# FPGA_Systems_Program.net
KiCad netlist of a schematic drawn in Altium Designer
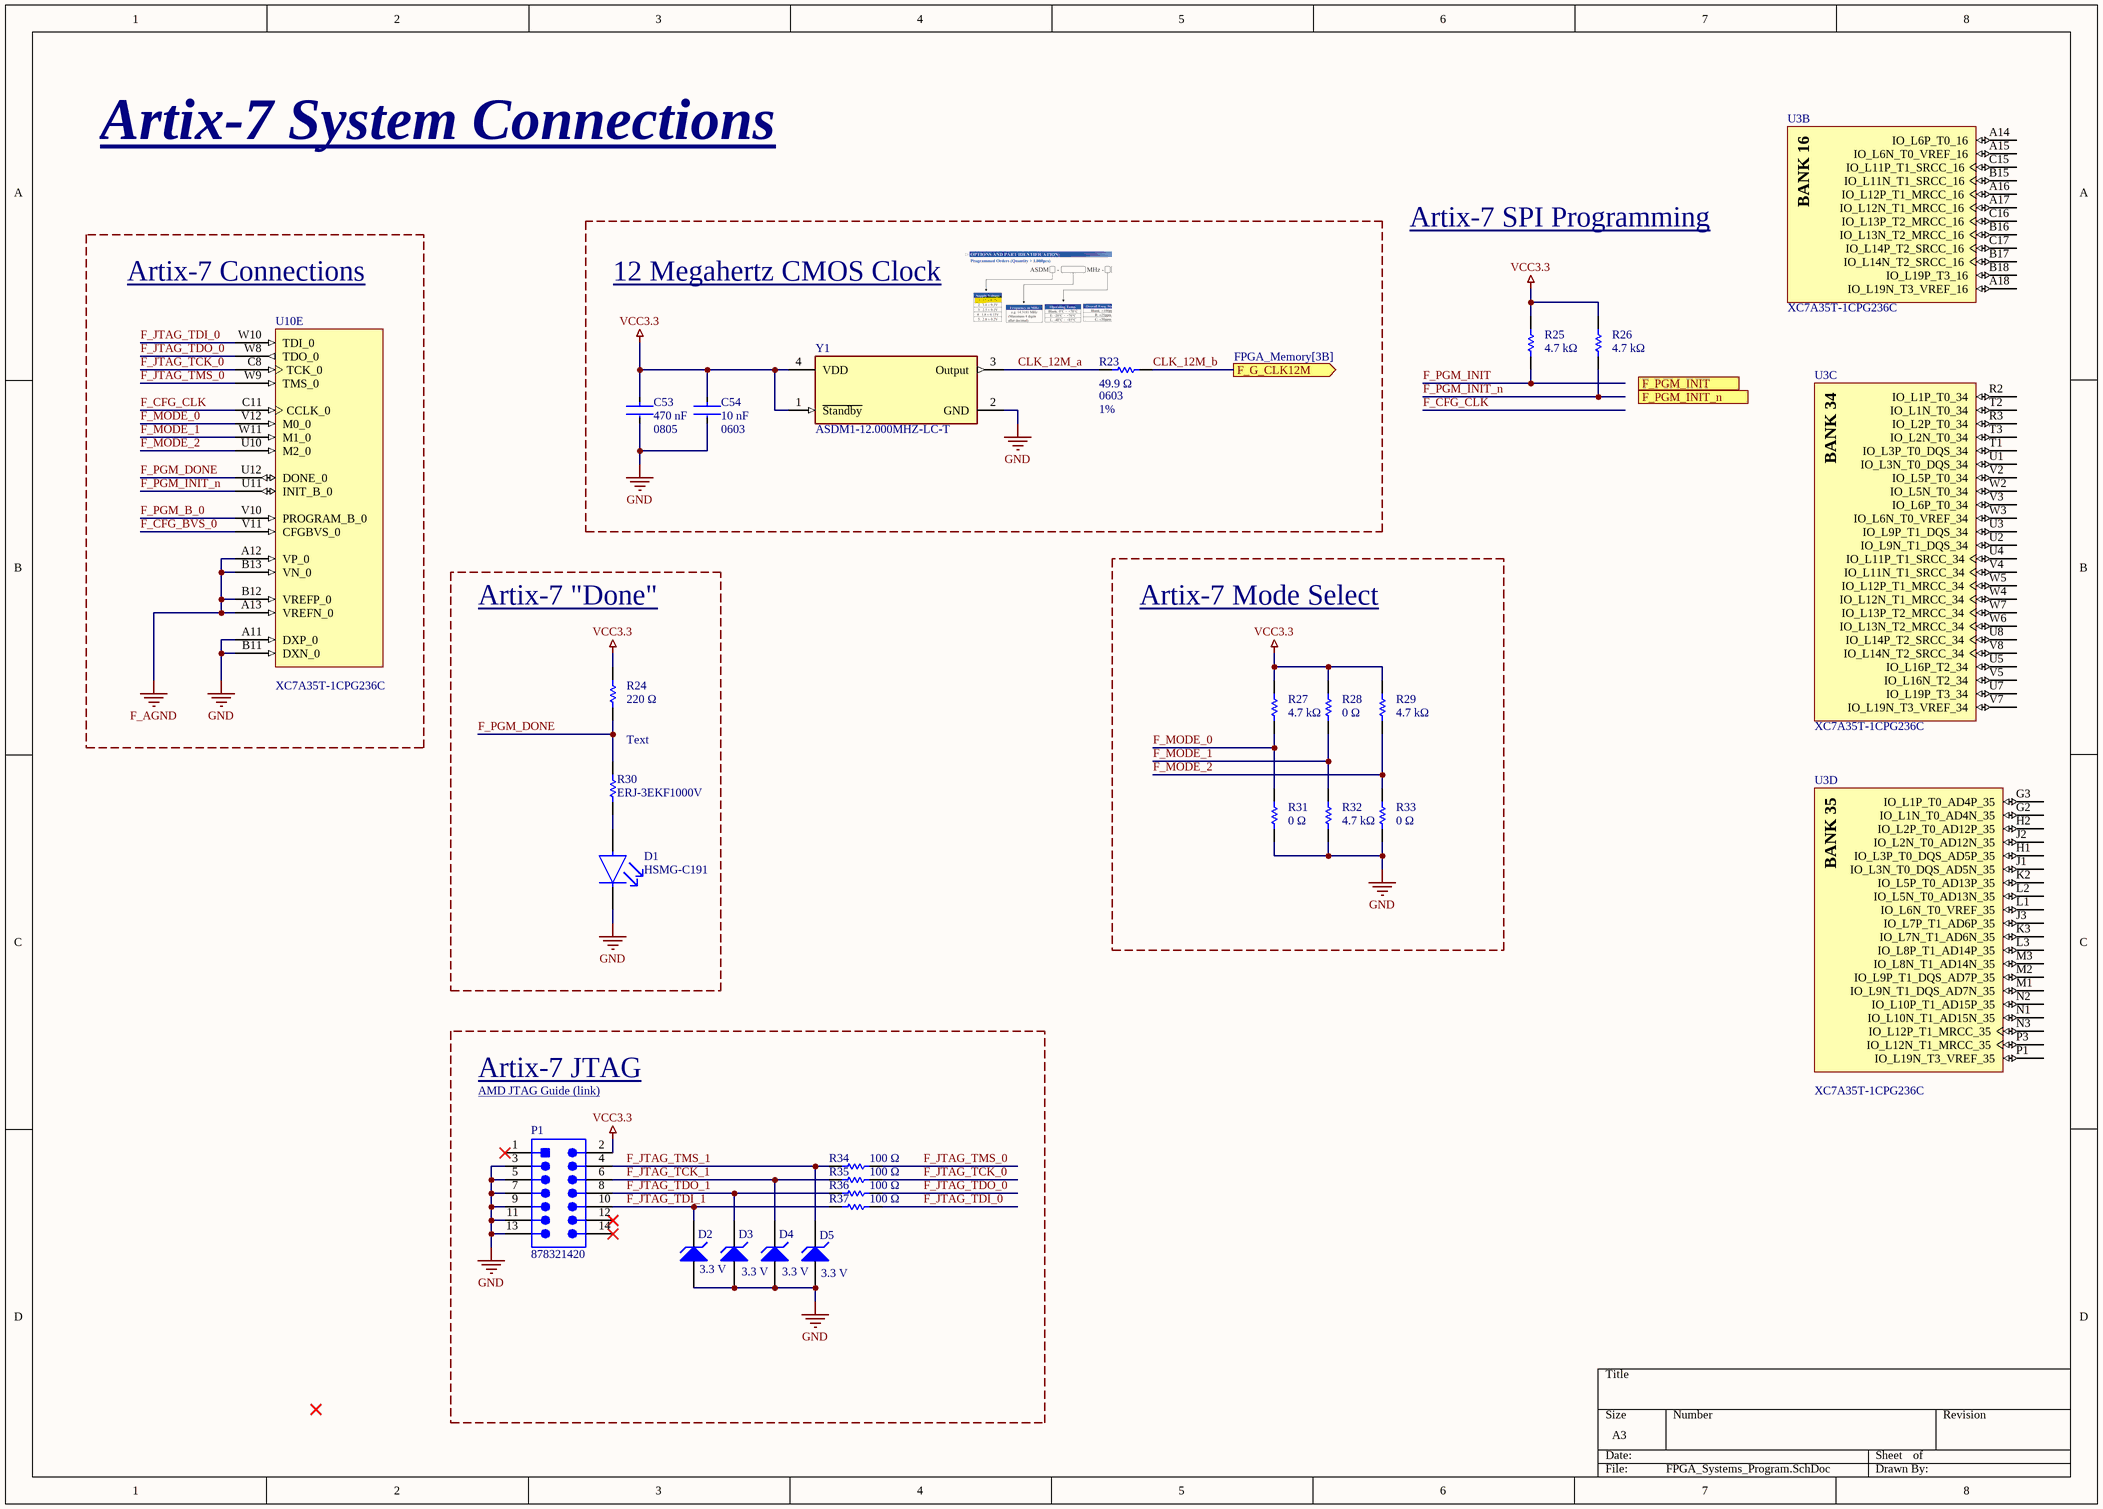
[diagram p0: FPGA_Systems_Program.SchDoc]

(export (version "E")
  (design (tool "Eeschema 10.0.6"))
  (components
    (comp (ref "C53")
      (value "CGA4J3X7R1H474M125AE")
      (footprint "FP-CGA4J-IPC_A")
      (description "Cap Ceramic 470nF 50V X7R 20% Pad SMD 0805 +125°C Automotive T/R")
      (fields
        (field (name "CASE CODE (IMPERIAL)") "0805")
        (field (name "TOLERANCE") "20%")
        (field (name "CAPACITANCE") "470 nF")
      )
      (libsource (lib "Altium Content Vault") (part "b4654b650e69147ec39a6b967a45e02"))
    )
    (comp (ref "C54")
      (value "EMK107SD103KA-T")
      (footprint "FP-0603-L_1_6_0_1-W_0_8_0-MFG")
      (description "None")
      (fields
        (field (name "CASE CODE (IMPERIAL)") "0603")
        (field (name "TOLERANCE") "10%")
        (field (name "CAPACITANCE") "10 nF")
      )
      (libsource (lib "Altium Content Vault") (part "02cd4be3c70576c341d710602a673aa"))
    )
    (comp (ref "D1")
      (value "HSMG-C191")
      (footprint "FP-HSMG-C191-MFG")
      (description "LED GREEN DIFFUSED CHIP SMD")
      (fields
        (field (name "MANUFACTURER") "Broadcom")
        (field (name "OCTOPART") "https://octopart.com/hsmg-c191-broadcom-71131308")
      )
      (libsource (lib "Altium Content Vault") (part "8706943c75ba83719d021d2fdc84c58"))
    )
    (comp (ref "D2")
      (value "1SMB5913BT3G")
      (footprint "ONSC-SMB-2-403A-03_H_V")
      (description "3 W Zener Voltage Regulator, 2-Pin SMB, Pb-Free, Tape and Reel")
      (fields (field (name "MANUFACTURER") "On Semiconductor") (field (name "VZ TYP (V)") "3.3 V"))
      (libsource (lib "Altium Content Vault") (part "ONSC-K1A2-2"))
    )
    (comp (ref "D3")
      (value "1SMB5913BT3G")
      (footprint "ONSC-SMB-2-403A-03_H_V")
      (description "3 W Zener Voltage Regulator, 2-Pin SMB, Pb-Free, Tape and Reel")
      (fields (field (name "MANUFACTURER") "On Semiconductor") (field (name "VZ TYP (V)") "3.3 V"))
      (libsource (lib "Altium Content Vault") (part "ONSC-K1A2-2"))
    )
    (comp (ref "D4")
      (value "1SMB5913BT3G")
      (footprint "ONSC-SMB-2-403A-03_H_V")
      (description "3 W Zener Voltage Regulator, 2-Pin SMB, Pb-Free, Tape and Reel")
      (fields (field (name "MANUFACTURER") "On Semiconductor") (field (name "VZ TYP (V)") "3.3 V"))
      (libsource (lib "Altium Content Vault") (part "ONSC-K1A2-2"))
    )
    (comp (ref "D5")
      (value "1SMB5913BT3G")
      (footprint "ONSC-SMB-2-403A-03_H_V")
      (description "3 W Zener Voltage Regulator, 2-Pin SMB, Pb-Free, Tape and Reel")
      (fields (field (name "MANUFACTURER") "On Semiconductor") (field (name "VZ TYP (V)") "3.3 V"))
      (libsource (lib "Altium Content Vault") (part "ONSC-K1A2-2"))
    )
    (comp (ref "P1")
      (value "878321420")
      (footprint "MOLX-878321420_V")
      (description "Male Header, Pitch 2 mm, 2 x 7 Position, Height 7.6 mm, -55 to 105 degC, RoHS")
      (fields (field (name "MANUFACTURER") "Molex"))
      (libsource (lib "Altium Content Vault") (part "CN-2P-M-R14"))
    )
    (comp (ref "R23")
      (value "49.9 Ω")
      (footprint "RESC1608X55X25NL10T15")
      (fields
        (field (name "PACKAGEREFERENCE") "0603")
        (field (name "TOLERANCE") "1%")
        (field (name "Comment") "RC0603FR-0749R9L")
      )
      (libsource (lib "Altium Content Vault") (part "RES-2"))
    )
    (comp (ref "R24")
      (value "ERJ-3EKF2200V")
      (footprint "RESC1608X55X30LL15T15")
      (description "Chip Resistor, 220 Ohm, +/- 1%, 0.1 W, -55 to 155 degC, 0603 (1608 Metric), RoHS, Tape and Reel")
      (fields (field (name "RESISTANCE") "220 Ω") (field (name "TOLERANCE") "1%"))
      (libsource (lib "Altium Content Vault") (part "RES-2"))
    )
    (comp (ref "R25")
      (value "ERJ-3EKF4701V")
      (footprint "RESC1608X55X30LL15T15")
      (fields
        (field (name "TOLERANCE") "1%")
        (field (name "POWER") "100mW")
        (field (name "RESISTANCE") "4.7 kΩ")
      )
      (libsource (lib "Personal Workspace") (part "RES-2"))
    )
    (comp (ref "R26")
      (value "ERJ-3EKF4701V")
      (footprint "RESC1608X55X30LL15T15")
      (fields
        (field (name "TOLERANCE") "1%")
        (field (name "POWER") "100mW")
        (field (name "RESISTANCE") "4.7 kΩ")
      )
      (libsource (lib "Personal Workspace") (part "RES-2"))
    )
    (comp (ref "R27")
      (value "ERJ-3EKF4701V")
      (footprint "RESC1608X55X30LL15T15")
      (fields
        (field (name "TOLERANCE") "1%")
        (field (name "POWER") "100mW")
        (field (name "RESISTANCE") "4.7 kΩ")
      )
      (libsource (lib "Personal Workspace") (part "RES-2"))
    )
    (comp (ref "R28")
      (value "ERJ-3EKF4701V")
      (footprint "RESC1608X55X30LL15T15")
      (fields
        (field (name "TOLERANCE") "1%")
        (field (name "POWER") "100mW")
        (field (name "RESISTANCE") "0 Ω")
      )
      (libsource (lib "Personal Workspace") (part "RES-2"))
    )
    (comp (ref "R29")
      (value "ERJ-3EKF4701V")
      (footprint "RESC1608X55X30LL15T15")
      (fields
        (field (name "TOLERANCE") "1%")
        (field (name "POWER") "100mW")
        (field (name "RESISTANCE") "4.7 kΩ")
      )
      (libsource (lib "Personal Workspace") (part "RES-2"))
    )
    (comp (ref "R30")
      (value "ERJ-3EKF1000V")
      (footprint "RESC1608X55X30LL15T15")
      (fields (field (name "MANUFACTURER") "Panasonic"))
      (libsource (lib "Altium Content Vault") (part "RES"))
    )
    (comp (ref "R31")
      (value "ERJ-3EKF4701V")
      (footprint "RESC1608X55X30LL15T15")
      (fields
        (field (name "TOLERANCE") "1%")
        (field (name "POWER") "100mW")
        (field (name "RESISTANCE") "0 Ω")
      )
      (libsource (lib "Personal Workspace") (part "RES-2"))
    )
    (comp (ref "R32")
      (value "ERJ-3EKF4701V")
      (footprint "RESC1608X55X30LL15T15")
      (fields
        (field (name "TOLERANCE") "1%")
        (field (name "POWER") "100mW")
        (field (name "RESISTANCE") "4.7 kΩ")
      )
      (libsource (lib "Personal Workspace") (part "RES-2"))
    )
    (comp (ref "R33")
      (value "ERJ-3EKF4701V")
      (footprint "RESC1608X55X30LL15T15")
      (fields
        (field (name "TOLERANCE") "1%")
        (field (name "POWER") "100mW")
        (field (name "RESISTANCE") "0 Ω")
      )
      (libsource (lib "Personal Workspace") (part "RES-2"))
    )
    (comp (ref "R34")
      (value "100 Ω")
      (footprint "RESC1608X55X30LL15T15")
      (fields (field (name "MANUFACTURER") "Panasonic") (field (name "PART NUMBER") "ERJ-3EKF1000V"))
      (libsource (lib "Altium Content Vault") (part "RES"))
    )
    (comp (ref "R35")
      (value "100 Ω")
      (footprint "RESC1608X55X30LL15T15")
      (fields (field (name "MANUFACTURER") "Panasonic") (field (name "PART NUMBER") "ERJ-3EKF1000V"))
      (libsource (lib "Altium Content Vault") (part "RES"))
    )
    (comp (ref "R36")
      (value "100 Ω")
      (footprint "RESC1608X55X30LL15T15")
      (fields (field (name "MANUFACTURER") "Panasonic") (field (name "PART NUMBER") "ERJ-3EKF1000V"))
      (libsource (lib "Altium Content Vault") (part "RES"))
    )
    (comp (ref "R37")
      (value "100 Ω")
      (footprint "RESC1608X55X30LL15T15")
      (fields (field (name "MANUFACTURER") "Panasonic") (field (name "PART NUMBER") "ERJ-3EKF1000V"))
      (libsource (lib "Altium Content Vault") (part "RES"))
    )
    (comp (ref "U3")
      (value "XC7A35T-1CPG236C")
      (footprint "CPG236")
      (description "Artix-7 FPGA, 106 User I/Os, 2 GTP, 238-Ball BGA, Speed Grade 1, Commercial Grade, Pb-Free")
      (fields (field (name "MANUFACTURER") "Xilinx"))
      (libsource (lib "Altium Content Vault") (part "XLNX-XC7A35T-CPG236"))
    )
    (comp (ref "U10")
      (value "XC7A35T-1CPG236C")
      (footprint "CPG236")
      (description "Artix-7 FPGA, 106 User I/Os, 2 GTP, 238-Ball BGA, Speed Grade 1, Commercial Grade, Pb-Free")
      (fields (field (name "MANUFACTURER") "Xilinx"))
      (libsource (lib "Altium Content Vault") (part "XLNX-XC7A35T-CPG236"))
    )
    (comp (ref "Y1")
      (value "ASDM1-12.000MHZ-LC-T")
      (footprint "FP-ASDM-ASDMB-MFG")
      (description "MEMS Oscillator 12MHz ±50ppm LVCMOS 3.3V SMD 2.5x2mm")
      (libsource (lib "Altium Content Vault") (part "d1c68ac5f38726358044f3b7e06346c"))
    )
  )
  (nets
    (net (code "1") (name "/CLK_12M_a") (class "Default")
      (node (ref "R23") (pin "1") (pinfunction "1_1") (pintype "passive"))
      (node (ref "Y1") (pin "3") (pinfunction "Output_3") (pintype "output"))
    )
    (net (code "2") (name "/CLK_12M_b") (class "Default")
      (node (ref "R23") (pin "2") (pinfunction "2_2") (pintype "passive"))
    )
    (net (code "3") (name "/F_CFG_BVS_0") (class "Default")
      (node (ref "U10") (pin "V11") (pinfunction "CFGBVS_0_V11") (pintype "input"))
    )
    (net (code "4") (name "/F_CFG_CLK") (class "Default")
      (node (ref "U10") (pin "C11") (pinfunction "CCLK_0_C11") (pintype "input"))
    )
    (net (code "5") (name "/F_JTAG_TCK_0") (class "Default")
      (node (ref "R35") (pin "2") (pinfunction "2_2") (pintype "passive"))
      (node (ref "U10") (pin "C8") (pinfunction "TCK_0_C8") (pintype "input"))
    )
    (net (code "6") (name "/F_JTAG_TCK_1") (class "Default")
      (node (ref "D4") (pin "1") (pinfunction "K_1") (pintype "passive"))
      (node (ref "P1") (pin "6") (pinfunction "6_6") (pintype "passive"))
      (node (ref "R35") (pin "1") (pinfunction "1_1") (pintype "passive"))
    )
    (net (code "7") (name "/F_JTAG_TDI_0") (class "Default")
      (node (ref "R37") (pin "2") (pinfunction "2_2") (pintype "passive"))
      (node (ref "U10") (pin "W10") (pinfunction "TDI_0_W10") (pintype "input"))
    )
    (net (code "8") (name "/F_JTAG_TDI_1") (class "Default")
      (node (ref "D2") (pin "1") (pinfunction "K_1") (pintype "passive"))
      (node (ref "P1") (pin "10") (pinfunction "10_10") (pintype "passive"))
      (node (ref "R37") (pin "1") (pinfunction "1_1") (pintype "passive"))
    )
    (net (code "9") (name "/F_JTAG_TDO_0") (class "Default")
      (node (ref "R36") (pin "2") (pinfunction "2_2") (pintype "passive"))
      (node (ref "U10") (pin "W8") (pinfunction "TDO_0_W8") (pintype "output"))
    )
    (net (code "10") (name "/F_JTAG_TDO_1") (class "Default")
      (node (ref "D3") (pin "1") (pinfunction "K_1") (pintype "passive"))
      (node (ref "P1") (pin "8") (pinfunction "8_8") (pintype "passive"))
      (node (ref "R36") (pin "1") (pinfunction "1_1") (pintype "passive"))
    )
    (net (code "11") (name "/F_JTAG_TMS_0") (class "Default")
      (node (ref "R34") (pin "2") (pinfunction "2_2") (pintype "passive"))
      (node (ref "U10") (pin "W9") (pinfunction "TMS_0_W9") (pintype "input"))
    )
    (net (code "12") (name "/F_JTAG_TMS_1") (class "Default")
      (node (ref "D5") (pin "1") (pinfunction "K_1") (pintype "passive"))
      (node (ref "P1") (pin "4") (pinfunction "4_4") (pintype "passive"))
      (node (ref "R34") (pin "1") (pinfunction "1_1") (pintype "passive"))
    )
    (net (code "13") (name "/F_MODE_0") (class "Default")
      (node (ref "R27") (pin "1") (pinfunction "1_1") (pintype "passive"))
      (node (ref "R31") (pin "2") (pinfunction "2_2") (pintype "passive"))
      (node (ref "U10") (pin "V12") (pinfunction "M0_0_V12") (pintype "input"))
    )
    (net (code "14") (name "/F_MODE_1") (class "Default")
      (node (ref "R28") (pin "1") (pinfunction "1_1") (pintype "passive"))
      (node (ref "R32") (pin "2") (pinfunction "2_2") (pintype "passive"))
      (node (ref "U10") (pin "W11") (pinfunction "M1_0_W11") (pintype "input"))
    )
    (net (code "15") (name "/F_MODE_2") (class "Default")
      (node (ref "R29") (pin "1") (pinfunction "1_1") (pintype "passive"))
      (node (ref "R33") (pin "2") (pinfunction "2_2") (pintype "passive"))
      (node (ref "U10") (pin "U10") (pinfunction "M2_0_U10") (pintype "input"))
    )
    (net (code "16") (name "/F_PGM_B_0") (class "Default")
      (node (ref "U10") (pin "V10") (pinfunction "PROGRAM_B_0_V10") (pintype "input"))
    )
    (net (code "17") (name "/F_PGM_DONE") (class "Default")
      (node (ref "R24") (pin "1") (pinfunction "1_1") (pintype "passive"))
      (node (ref "R30") (pin "2") (pinfunction "2_2") (pintype "passive"))
      (node (ref "U10") (pin "U12") (pinfunction "DONE_0_U12") (pintype "bidirectional"))
    )
    (net (code "18") (name "/F_PGM_INIT") (class "Default")
      (node (ref "R25") (pin "1") (pinfunction "1_1") (pintype "passive"))
    )
    (net (code "19") (name "/F_PGM_INIT_n") (class "Default")
      (node (ref "R26") (pin "1") (pinfunction "1_1") (pintype "passive"))
      (node (ref "U10") (pin "U11") (pinfunction "INIT_B_0_U11") (pintype "bidirectional"))
    )
    (net (code "20") (name "F_AGND") (class "Default")
      (node (ref "U10") (pin "A12") (pinfunction "VP_0_A12") (pintype "input"))
      (node (ref "U10") (pin "A13") (pinfunction "VREFN_0_A13") (pintype "input"))
      (node (ref "U10") (pin "B12") (pinfunction "VREFP_0_B12") (pintype "input"))
      (node (ref "U10") (pin "B13") (pinfunction "VN_0_B13") (pintype "input"))
    )
    (net (code "21") (name "GND") (class "Default")
      (node (ref "C53") (pin "2") (pinfunction "2_2") (pintype "passive"))
      (node (ref "C54") (pin "2") (pinfunction "2_2") (pintype "passive"))
      (node (ref "D1") (pin "1") (pinfunction "C_1") (pintype "passive"))
      (node (ref "D2") (pin "2") (pinfunction "A_2") (pintype "passive"))
      (node (ref "D3") (pin "2") (pinfunction "A_2") (pintype "passive"))
      (node (ref "D4") (pin "2") (pinfunction "A_2") (pintype "passive"))
      (node (ref "D5") (pin "2") (pinfunction "A_2") (pintype "passive"))
      (node (ref "P1") (pin "11") (pinfunction "11_11") (pintype "passive"))
      (node (ref "P1") (pin "13") (pinfunction "13_13") (pintype "passive"))
      (node (ref "P1") (pin "3") (pinfunction "3_3") (pintype "passive"))
      (node (ref "P1") (pin "5") (pinfunction "5_5") (pintype "passive"))
      (node (ref "P1") (pin "7") (pinfunction "7_7") (pintype "passive"))
      (node (ref "P1") (pin "9") (pinfunction "9_9") (pintype "passive"))
      (node (ref "R31") (pin "1") (pinfunction "1_1") (pintype "passive"))
      (node (ref "R32") (pin "1") (pinfunction "1_1") (pintype "passive"))
      (node (ref "R33") (pin "1") (pinfunction "1_1") (pintype "passive"))
      (node (ref "U10") (pin "A11") (pinfunction "DXP_0_A11") (pintype "input"))
      (node (ref "U10") (pin "B11") (pinfunction "DXN_0_B11") (pintype "input"))
      (node (ref "Y1") (pin "2") (pinfunction "GND_2") (pintype "power_in"))
    )
    (net (code "22") (name "Net-(D1-A)") (class "Default")
      (node (ref "D1") (pin "2") (pinfunction "A_2") (pintype "passive"))
      (node (ref "R30") (pin "1") (pinfunction "1_1") (pintype "passive"))
    )
    (net (code "23") (name "VCC3.3") (class "Default")
      (node (ref "C53") (pin "1") (pinfunction "1_1") (pintype "passive"))
      (node (ref "C54") (pin "1") (pinfunction "1_1") (pintype "passive"))
      (node (ref "P1") (pin "2") (pinfunction "2_2") (pintype "passive"))
      (node (ref "R24") (pin "2") (pinfunction "2_2") (pintype "passive"))
      (node (ref "R25") (pin "2") (pinfunction "2_2") (pintype "passive"))
      (node (ref "R26") (pin "2") (pinfunction "2_2") (pintype "passive"))
      (node (ref "R27") (pin "2") (pinfunction "2_2") (pintype "passive"))
      (node (ref "R28") (pin "2") (pinfunction "2_2") (pintype "passive"))
      (node (ref "R29") (pin "2") (pinfunction "2_2") (pintype "passive"))
      (node (ref "Y1") (pin "1") (pinfunction "~{Standby}_1") (pintype "input"))
      (node (ref "Y1") (pin "4") (pinfunction "VDD_4") (pintype "power_in"))
    )
    (net (code "24") (name "unconnected-(P1-Pad1)") (class "Default")
      (node (ref "P1") (pin "1") (pinfunction "1_1") (pintype "passive+no_connect"))
    )
    (net (code "25") (name "unconnected-(P1-Pad12)") (class "Default")
      (node (ref "P1") (pin "12") (pinfunction "12_12") (pintype "passive+no_connect"))
    )
    (net (code "26") (name "unconnected-(P1-Pad14)") (class "Default")
      (node (ref "P1") (pin "14") (pinfunction "14_14") (pintype "passive+no_connect"))
    )
    (net (code "27") (name "unconnected-(U3B-IO_L6N_T0_VREF_16-PadA15)") (class "Default")
      (node (ref "U3") (pin "A15") (pinfunction "IO_L6N_T0_VREF_16_A15") (pintype "bidirectional"))
    )
    (net (code "28") (name "unconnected-(U3B-IO_L6P_T0_16-PadA14)") (class "Default")
      (node (ref "U3") (pin "A14") (pinfunction "IO_L6P_T0_16_A14") (pintype "bidirectional"))
    )
    (net (code "29") (name "unconnected-(U3B-IO_L11N_T1_SRCC_16-PadB15)") (class "Default")
      (node (ref "U3") (pin "B15") (pinfunction "IO_L11N_T1_SRCC_16_B15") (pintype "bidirectional"))
    )
    (net (code "30") (name "unconnected-(U3B-IO_L11P_T1_SRCC_16-PadC15)") (class "Default")
      (node (ref "U3") (pin "C15") (pinfunction "IO_L11P_T1_SRCC_16_C15") (pintype "bidirectional"))
    )
    (net (code "31") (name "unconnected-(U3B-IO_L12N_T1_MRCC_16-PadA17)") (class "Default")
      (node (ref "U3") (pin "A17") (pinfunction "IO_L12N_T1_MRCC_16_A17") (pintype "bidirectional"))
    )
    (net (code "32") (name "unconnected-(U3B-IO_L12P_T1_MRCC_16-PadA16)") (class "Default")
      (node (ref "U3") (pin "A16") (pinfunction "IO_L12P_T1_MRCC_16_A16") (pintype "bidirectional"))
    )
    (net (code "33") (name "unconnected-(U3B-IO_L13N_T2_MRCC_16-PadB16)") (class "Default")
      (node (ref "U3") (pin "B16") (pinfunction "IO_L13N_T2_MRCC_16_B16") (pintype "bidirectional"))
    )
    (net (code "34") (name "unconnected-(U3B-IO_L13P_T2_MRCC_16-PadC16)") (class "Default")
      (node (ref "U3") (pin "C16") (pinfunction "IO_L13P_T2_MRCC_16_C16") (pintype "bidirectional"))
    )
    (net (code "35") (name "unconnected-(U3B-IO_L14N_T2_SRCC_16-PadB17)") (class "Default")
      (node (ref "U3") (pin "B17") (pinfunction "IO_L14N_T2_SRCC_16_B17") (pintype "bidirectional"))
    )
    (net (code "36") (name "unconnected-(U3B-IO_L14P_T2_SRCC_16-PadC17)") (class "Default")
      (node (ref "U3") (pin "C17") (pinfunction "IO_L14P_T2_SRCC_16_C17") (pintype "bidirectional"))
    )
    (net (code "37") (name "unconnected-(U3B-IO_L19N_T3_VREF_16-PadA18)") (class "Default")
      (node (ref "U3") (pin "A18") (pinfunction "IO_L19N_T3_VREF_16_A18") (pintype "bidirectional"))
    )
    (net (code "38") (name "unconnected-(U3B-IO_L19P_T3_16-PadB18)") (class "Default")
      (node (ref "U3") (pin "B18") (pinfunction "IO_L19P_T3_16_B18") (pintype "bidirectional"))
    )
    (net (code "39") (name "unconnected-(U3C-IO_L1N_T0_34-PadT2)") (class "Default")
      (node (ref "U3") (pin "T2") (pinfunction "IO_L1N_T0_34_T2") (pintype "bidirectional"))
    )
    (net (code "40") (name "unconnected-(U3C-IO_L1P_T0_34-PadR2)") (class "Default")
      (node (ref "U3") (pin "R2") (pinfunction "IO_L1P_T0_34_R2") (pintype "bidirectional"))
    )
    (net (code "41") (name "unconnected-(U3C-IO_L2N_T0_34-PadT3)") (class "Default")
      (node (ref "U3") (pin "T3") (pinfunction "IO_L2N_T0_34_T3") (pintype "bidirectional"))
    )
    (net (code "42") (name "unconnected-(U3C-IO_L2P_T0_34-PadR3)") (class "Default")
      (node (ref "U3") (pin "R3") (pinfunction "IO_L2P_T0_34_R3") (pintype "bidirectional"))
    )
    (net (code "43") (name "unconnected-(U3C-IO_L3N_T0_DQS_34-PadU1)") (class "Default")
      (node (ref "U3") (pin "U1") (pinfunction "IO_L3N_T0_DQS_34_U1") (pintype "bidirectional"))
    )
    (net (code "44") (name "unconnected-(U3C-IO_L3P_T0_DQS_34-PadT1)") (class "Default")
      (node (ref "U3") (pin "T1") (pinfunction "IO_L3P_T0_DQS_34_T1") (pintype "bidirectional"))
    )
    (net (code "45") (name "unconnected-(U3C-IO_L5N_T0_34-PadW2)") (class "Default")
      (node (ref "U3") (pin "W2") (pinfunction "IO_L5N_T0_34_W2") (pintype "bidirectional"))
    )
    (net (code "46") (name "unconnected-(U3C-IO_L5P_T0_34-PadV2)") (class "Default")
      (node (ref "U3") (pin "V2") (pinfunction "IO_L5P_T0_34_V2") (pintype "bidirectional"))
    )
    (net (code "47") (name "unconnected-(U3C-IO_L6N_T0_VREF_34-PadW3)") (class "Default")
      (node (ref "U3") (pin "W3") (pinfunction "IO_L6N_T0_VREF_34_W3") (pintype "bidirectional"))
    )
    (net (code "48") (name "unconnected-(U3C-IO_L6P_T0_34-PadV3)") (class "Default")
      (node (ref "U3") (pin "V3") (pinfunction "IO_L6P_T0_34_V3") (pintype "bidirectional"))
    )
    (net (code "49") (name "unconnected-(U3C-IO_L9N_T1_DQS_34-PadU2)") (class "Default")
      (node (ref "U3") (pin "U2") (pinfunction "IO_L9N_T1_DQS_34_U2") (pintype "bidirectional"))
    )
    (net (code "50") (name "unconnected-(U3C-IO_L9P_T1_DQS_34-PadU3)") (class "Default")
      (node (ref "U3") (pin "U3") (pinfunction "IO_L9P_T1_DQS_34_U3") (pintype "bidirectional"))
    )
    (net (code "51") (name "unconnected-(U3C-IO_L11N_T1_SRCC_34-PadV4)") (class "Default")
      (node (ref "U3") (pin "V4") (pinfunction "IO_L11N_T1_SRCC_34_V4") (pintype "bidirectional"))
    )
    (net (code "52") (name "unconnected-(U3C-IO_L11P_T1_SRCC_34-PadU4)") (class "Default")
      (node (ref "U3") (pin "U4") (pinfunction "IO_L11P_T1_SRCC_34_U4") (pintype "bidirectional"))
    )
    (net (code "53") (name "unconnected-(U3C-IO_L12N_T1_MRCC_34-PadW4)") (class "Default")
      (node (ref "U3") (pin "W4") (pinfunction "IO_L12N_T1_MRCC_34_W4") (pintype "bidirectional"))
    )
    (net (code "54") (name "unconnected-(U3C-IO_L12P_T1_MRCC_34-PadW5)") (class "Default")
      (node (ref "U3") (pin "W5") (pinfunction "IO_L12P_T1_MRCC_34_W5") (pintype "bidirectional"))
    )
    (net (code "55") (name "unconnected-(U3C-IO_L13N_T2_MRCC_34-PadW6)") (class "Default")
      (node (ref "U3") (pin "W6") (pinfunction "IO_L13N_T2_MRCC_34_W6") (pintype "bidirectional"))
    )
    (net (code "56") (name "unconnected-(U3C-IO_L13P_T2_MRCC_34-PadW7)") (class "Default")
      (node (ref "U3") (pin "W7") (pinfunction "IO_L13P_T2_MRCC_34_W7") (pintype "bidirectional"))
    )
    (net (code "57") (name "unconnected-(U3C-IO_L14N_T2_SRCC_34-PadV8)") (class "Default")
      (node (ref "U3") (pin "V8") (pinfunction "IO_L14N_T2_SRCC_34_V8") (pintype "bidirectional"))
    )
    (net (code "58") (name "unconnected-(U3C-IO_L14P_T2_SRCC_34-PadU8)") (class "Default")
      (node (ref "U3") (pin "U8") (pinfunction "IO_L14P_T2_SRCC_34_U8") (pintype "bidirectional"))
    )
    (net (code "59") (name "unconnected-(U3C-IO_L16N_T2_34-PadV5)") (class "Default")
      (node (ref "U3") (pin "V5") (pinfunction "IO_L16N_T2_34_V5") (pintype "bidirectional"))
    )
    (net (code "60") (name "unconnected-(U3C-IO_L16P_T2_34-PadU5)") (class "Default")
      (node (ref "U3") (pin "U5") (pinfunction "IO_L16P_T2_34_U5") (pintype "bidirectional"))
    )
    (net (code "61") (name "unconnected-(U3C-IO_L19N_T3_VREF_34-PadV7)") (class "Default")
      (node (ref "U3") (pin "V7") (pinfunction "IO_L19N_T3_VREF_34_V7") (pintype "bidirectional"))
    )
    (net (code "62") (name "unconnected-(U3C-IO_L19P_T3_34-PadU7)") (class "Default")
      (node (ref "U3") (pin "U7") (pinfunction "IO_L19P_T3_34_U7") (pintype "bidirectional"))
    )
    (net (code "63") (name "unconnected-(U3D-IO_L1N_T0_AD4N_35-PadG2)") (class "Default")
      (node (ref "U3") (pin "G2") (pinfunction "IO_L1N_T0_AD4N_35_G2") (pintype "bidirectional"))
    )
    (net (code "64") (name "unconnected-(U3D-IO_L1P_T0_AD4P_35-PadG3)") (class "Default")
      (node (ref "U3") (pin "G3") (pinfunction "IO_L1P_T0_AD4P_35_G3") (pintype "bidirectional"))
    )
    (net (code "65") (name "unconnected-(U3D-IO_L2N_T0_AD12N_35-PadJ2)") (class "Default")
      (node (ref "U3") (pin "J2") (pinfunction "IO_L2N_T0_AD12N_35_J2") (pintype "bidirectional"))
    )
    (net (code "66") (name "unconnected-(U3D-IO_L2P_T0_AD12P_35-PadH2)") (class "Default")
      (node (ref "U3") (pin "H2") (pinfunction "IO_L2P_T0_AD12P_35_H2") (pintype "bidirectional"))
    )
    (net (code "67") (name "unconnected-(U3D-IO_L3N_T0_DQS_AD5N_35-PadJ1)") (class "Default")
      (node (ref "U3") (pin "J1") (pinfunction "IO_L3N_T0_DQS_AD5N_35_J1") (pintype "bidirectional"))
    )
    (net (code "68") (name "unconnected-(U3D-IO_L3P_T0_DQS_AD5P_35-PadH1)") (class "Default")
      (node (ref "U3") (pin "H1") (pinfunction "IO_L3P_T0_DQS_AD5P_35_H1") (pintype "bidirectional"))
    )
    (net (code "69") (name "unconnected-(U3D-IO_L5N_T0_AD13N_35-PadL2)") (class "Default")
      (node (ref "U3") (pin "L2") (pinfunction "IO_L5N_T0_AD13N_35_L2") (pintype "bidirectional"))
    )
    (net (code "70") (name "unconnected-(U3D-IO_L5P_T0_AD13P_35-PadK2)") (class "Default")
      (node (ref "U3") (pin "K2") (pinfunction "IO_L5P_T0_AD13P_35_K2") (pintype "bidirectional"))
    )
    (net (code "71") (name "unconnected-(U3D-IO_L6N_T0_VREF_35-PadL1)") (class "Default")
      (node (ref "U3") (pin "L1") (pinfunction "IO_L6N_T0_VREF_35_L1") (pintype "bidirectional"))
    )
    (net (code "72") (name "unconnected-(U3D-IO_L7N_T1_AD6N_35-PadK3)") (class "Default")
      (node (ref "U3") (pin "K3") (pinfunction "IO_L7N_T1_AD6N_35_K3") (pintype "bidirectional"))
    )
    (net (code "73") (name "unconnected-(U3D-IO_L7P_T1_AD6P_35-PadJ3)") (class "Default")
      (node (ref "U3") (pin "J3") (pinfunction "IO_L7P_T1_AD6P_35_J3") (pintype "bidirectional"))
    )
    (net (code "74") (name "unconnected-(U3D-IO_L8N_T1_AD14N_35-PadM3)") (class "Default")
      (node (ref "U3") (pin "M3") (pinfunction "IO_L8N_T1_AD14N_35_M3") (pintype "bidirectional"))
    )
    (net (code "75") (name "unconnected-(U3D-IO_L8P_T1_AD14P_35-PadL3)") (class "Default")
      (node (ref "U3") (pin "L3") (pinfunction "IO_L8P_T1_AD14P_35_L3") (pintype "bidirectional"))
    )
    (net (code "76") (name "unconnected-(U3D-IO_L9N_T1_DQS_AD7N_35-PadM1)") (class "Default")
      (node (ref "U3") (pin "M1") (pinfunction "IO_L9N_T1_DQS_AD7N_35_M1") (pintype "bidirectional"))
    )
    (net (code "77") (name "unconnected-(U3D-IO_L9P_T1_DQS_AD7P_35-PadM2)") (class "Default")
      (node (ref "U3") (pin "M2") (pinfunction "IO_L9P_T1_DQS_AD7P_35_M2") (pintype "bidirectional"))
    )
    (net (code "78") (name "unconnected-(U3D-IO_L10N_T1_AD15N_35-PadN1)") (class "Default")
      (node (ref "U3") (pin "N1") (pinfunction "IO_L10N_T1_AD15N_35_N1") (pintype "bidirectional"))
    )
    (net (code "79") (name "unconnected-(U3D-IO_L10P_T1_AD15P_35-PadN2)") (class "Default")
      (node (ref "U3") (pin "N2") (pinfunction "IO_L10P_T1_AD15P_35_N2") (pintype "bidirectional"))
    )
    (net (code "80") (name "unconnected-(U3D-IO_L12N_T1_MRCC_35-PadP3)") (class "Default")
      (node (ref "U3") (pin "P3") (pinfunction "IO_L12N_T1_MRCC_35_P3") (pintype "bidirectional"))
    )
    (net (code "81") (name "unconnected-(U3D-IO_L12P_T1_MRCC_35-PadN3)") (class "Default")
      (node (ref "U3") (pin "N3") (pinfunction "IO_L12P_T1_MRCC_35_N3") (pintype "bidirectional"))
    )
    (net (code "82") (name "unconnected-(U3D-IO_L19N_T3_VREF_35-PadP1)") (class "Default")
      (node (ref "U3") (pin "P1") (pinfunction "IO_L19N_T3_VREF_35_P1") (pintype "bidirectional"))
    )
  )
)
